# lcd_booster-old.net
KiCad netlist of a schematic drawn in EAGLE
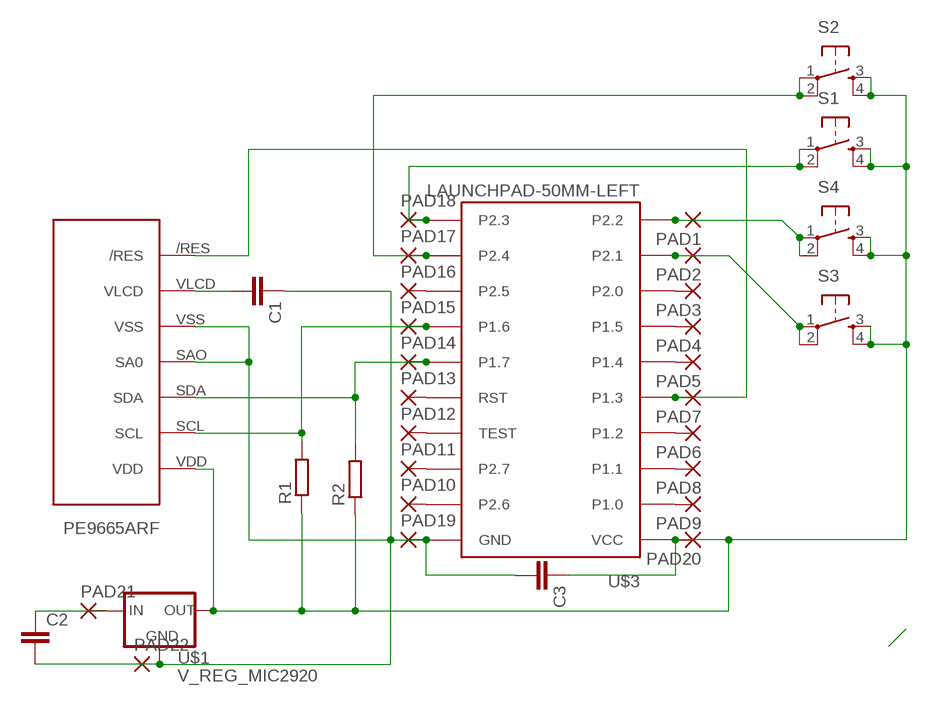
[diagram p0: schematic, sheet 1]

(export (version "E")
  (design (tool "Eeschema 10.0.6"))
  (components
    (comp (ref "C1")
      (value "C-EUC1206")
      (footprint "eagle-import:C1206")
      (libsource (lib "eagle-import") (part "C-EUC1206"))
    )
    (comp (ref "C2")
      (value "C-EUC1206")
      (footprint "eagle-import:C1206")
      (libsource (lib "eagle-import") (part "C-EUC1206"))
    )
    (comp (ref "C3")
      (value "C-EUC1206")
      (footprint "eagle-import:C1206")
      (libsource (lib "eagle-import") (part "C-EUC1206"))
    )
    (comp (ref "PAD1")
      (value "1,6/0,9")
      (footprint "eagle-import:1,6_0,9")
      (libsource (lib "eagle-import") (part "1,6/0,9"))
    )
    (comp (ref "PAD2")
      (value "1,6/0,9")
      (footprint "eagle-import:1,6_0,9")
      (libsource (lib "eagle-import") (part "1,6/0,9"))
    )
    (comp (ref "PAD3")
      (value "1,6/0,9")
      (footprint "eagle-import:1,6_0,9")
      (libsource (lib "eagle-import") (part "1,6/0,9"))
    )
    (comp (ref "PAD4")
      (value "1,6/0,9")
      (footprint "eagle-import:1,6_0,9")
      (libsource (lib "eagle-import") (part "1,6/0,9"))
    )
    (comp (ref "PAD5")
      (value "1,6/0,9")
      (footprint "eagle-import:1,6_0,9")
      (libsource (lib "eagle-import") (part "1,6/0,9"))
    )
    (comp (ref "PAD6")
      (value "1,6/0,9")
      (footprint "eagle-import:1,6_0,9")
      (libsource (lib "eagle-import") (part "1,6/0,9"))
    )
    (comp (ref "PAD7")
      (value "1,6/0,9")
      (footprint "eagle-import:1,6_0,9")
      (libsource (lib "eagle-import") (part "1,6/0,9"))
    )
    (comp (ref "PAD8")
      (value "1,6/0,9")
      (footprint "eagle-import:1,6_0,9")
      (libsource (lib "eagle-import") (part "1,6/0,9"))
    )
    (comp (ref "PAD9")
      (value "1,6/0,9")
      (footprint "eagle-import:1,6_0,9")
      (libsource (lib "eagle-import") (part "1,6/0,9"))
    )
    (comp (ref "PAD10")
      (value "1,6/0,9")
      (footprint "eagle-import:1,6_0,9")
      (libsource (lib "eagle-import") (part "1,6/0,9"))
    )
    (comp (ref "PAD11")
      (value "1,6/0,9")
      (footprint "eagle-import:1,6_0,9")
      (libsource (lib "eagle-import") (part "1,6/0,9"))
    )
    (comp (ref "PAD12")
      (value "1,6/0,9")
      (footprint "eagle-import:1,6_0,9")
      (libsource (lib "eagle-import") (part "1,6/0,9"))
    )
    (comp (ref "PAD13")
      (value "1,6/0,9")
      (footprint "eagle-import:1,6_0,9")
      (libsource (lib "eagle-import") (part "1,6/0,9"))
    )
    (comp (ref "PAD14")
      (value "1,6/0,9")
      (footprint "eagle-import:1,6_0,9")
      (libsource (lib "eagle-import") (part "1,6/0,9"))
    )
    (comp (ref "PAD15")
      (value "1,6/0,9")
      (footprint "eagle-import:1,6_0,9")
      (libsource (lib "eagle-import") (part "1,6/0,9"))
    )
    (comp (ref "PAD16")
      (value "1,6/0,9")
      (footprint "eagle-import:1,6_0,9")
      (libsource (lib "eagle-import") (part "1,6/0,9"))
    )
    (comp (ref "PAD17")
      (value "1,6/0,9")
      (footprint "eagle-import:1,6_0,9")
      (libsource (lib "eagle-import") (part "1,6/0,9"))
    )
    (comp (ref "PAD18")
      (value "1,6/0,9")
      (footprint "eagle-import:1,6_0,9")
      (libsource (lib "eagle-import") (part "1,6/0,9"))
    )
    (comp (ref "PAD19")
      (value "1,6/0,9")
      (footprint "eagle-import:1,6_0,9")
      (libsource (lib "eagle-import") (part "1,6/0,9"))
    )
    (comp (ref "PAD20")
      (value "1,6/0,9")
      (footprint "eagle-import:1,6_0,9")
      (libsource (lib "eagle-import") (part "1,6/0,9"))
    )
    (comp (ref "PAD21")
      (value "1,6/0,9")
      (footprint "eagle-import:1,6_0,9")
      (libsource (lib "eagle-import") (part "1,6/0,9"))
    )
    (comp (ref "PAD22")
      (value "1,6/0,9")
      (footprint "eagle-import:1,6_0,9")
      (libsource (lib "eagle-import") (part "1,6/0,9"))
    )
    (comp (ref "R1")
      (value "R-EU_M1206")
      (footprint "eagle-import:M1206")
      (libsource (lib "eagle-import") (part "R-EU_M1206"))
    )
    (comp (ref "R2")
      (value "R-EU_M1206")
      (footprint "eagle-import:M1206")
      (libsource (lib "eagle-import") (part "R-EU_M1206"))
    )
    (comp (ref "S1")
      (value "TAC_SWITCHPTH")
      (footprint "eagle-import:TACTILE-PTH")
      (libsource (lib "eagle-import") (part "TAC_SWITCHPTH"))
    )
    (comp (ref "S2")
      (value "TAC_SWITCHPTH")
      (footprint "eagle-import:TACTILE-PTH")
      (libsource (lib "eagle-import") (part "TAC_SWITCHPTH"))
    )
    (comp (ref "S3")
      (value "TAC_SWITCHPTH")
      (footprint "eagle-import:TACTILE-PTH")
      (libsource (lib "eagle-import") (part "TAC_SWITCHPTH"))
    )
    (comp (ref "S4")
      (value "TAC_SWITCHPTH")
      (footprint "eagle-import:TACTILE-PTH")
      (libsource (lib "eagle-import") (part "TAC_SWITCHPTH"))
    )
    (comp (ref "U$1")
      (value "V_REG_MIC2920")
      (footprint "eagle-import:SOT223")
      (libsource (lib "eagle-import") (part "V_REG_MIC2920"))
    )
    (comp (ref "U$2")
      (value "PE9665ARF")
      (footprint "eagle-import:PE9665ARF")
      (libsource (lib "eagle-import") (part "PE9665ARF"))
    )
    (comp (ref "U$3")
      (value "LAUNCHPAD-50MM-LEFT")
      (footprint "eagle-import:LAUNCHPAD-50MM-LEFT")
      (libsource (lib "eagle-import") (part "LAUNCHPAD-50MM-LEFT"))
    )
  )
  (nets
    (net (code "1") (name "Net-(C1-Pad2)") (class "Default")
      (node (ref "C1") (pin "2") (pinfunction "2_2") (pintype "passive"))
      (node (ref "U$2") (pin "VLCD") (pinfunction "VLCD_VLCD") (pintype "bidirectional"))
    )
    (net (code "2") (name "Net-(PAD1-P)") (class "Default")
      (node (ref "PAD1") (pin "1") (pinfunction "P_1") (pintype "passive"))
      (node (ref "S4") (pin "1") (pinfunction "1_1") (pintype "passive"))
      (node (ref "S4") (pin "2") (pinfunction "2_2") (pintype "passive"))
      (node (ref "U$3") (pin "P2.2") (pinfunction "P2.2_P2.2") (pintype "bidirectional"))
    )
    (net (code "3") (name "Net-(PAD2-P)") (class "Default")
      (node (ref "PAD2") (pin "1") (pinfunction "P_1") (pintype "passive"))
      (node (ref "S3") (pin "1") (pinfunction "1_1") (pintype "passive"))
      (node (ref "S3") (pin "2") (pinfunction "2_2") (pintype "passive"))
      (node (ref "U$3") (pin "P2.1") (pinfunction "P2.1_P2.1") (pintype "bidirectional"))
    )
    (net (code "4") (name "Net-(PAD3-P)") (class "Default")
      (node (ref "PAD3") (pin "1") (pinfunction "P_1") (pintype "passive"))
      (node (ref "U$3") (pin "P2.0") (pinfunction "P2.0_P2.0") (pintype "bidirectional"))
    )
    (net (code "5") (name "Net-(PAD4-P)") (class "Default")
      (node (ref "PAD4") (pin "1") (pinfunction "P_1") (pintype "passive"))
      (node (ref "U$3") (pin "P1.5") (pinfunction "P1.5_P1.5") (pintype "bidirectional"))
    )
    (net (code "6") (name "Net-(PAD5-P)") (class "Default")
      (node (ref "PAD5") (pin "1") (pinfunction "P_1") (pintype "passive"))
      (node (ref "U$3") (pin "P1.4") (pinfunction "P1.4_P1.4") (pintype "bidirectional"))
    )
    (net (code "7") (name "Net-(PAD6-P)") (class "Default")
      (node (ref "PAD6") (pin "1") (pinfunction "P_1") (pintype "passive"))
      (node (ref "U$3") (pin "P1.2") (pinfunction "P1.2_P1.2") (pintype "bidirectional"))
    )
    (net (code "8") (name "Net-(PAD7-P)") (class "Default")
      (node (ref "PAD7") (pin "1") (pinfunction "P_1") (pintype "passive"))
      (node (ref "U$2") (pin "/RES") (pinfunction "/RES_/RES") (pintype "bidirectional"))
      (node (ref "U$3") (pin "P1.3") (pinfunction "P1.3_P1.3") (pintype "bidirectional"))
    )
    (net (code "9") (name "Net-(PAD8-P)") (class "Default")
      (node (ref "PAD8") (pin "1") (pinfunction "P_1") (pintype "passive"))
      (node (ref "U$3") (pin "P1.1") (pinfunction "P1.1_P1.1") (pintype "bidirectional"))
    )
    (net (code "10") (name "Net-(PAD9-P)") (class "Default")
      (node (ref "PAD9") (pin "1") (pinfunction "P_1") (pintype "passive"))
      (node (ref "U$3") (pin "P1.0") (pinfunction "P1.0_P1.0") (pintype "bidirectional"))
    )
    (net (code "11") (name "Net-(PAD10-P)") (class "Default")
      (node (ref "PAD10") (pin "1") (pinfunction "P_1") (pintype "passive"))
      (node (ref "U$3") (pin "P2.6") (pinfunction "P2.6_P2.6") (pintype "bidirectional"))
    )
    (net (code "12") (name "Net-(PAD11-P)") (class "Default")
      (node (ref "PAD11") (pin "1") (pinfunction "P_1") (pintype "passive"))
      (node (ref "U$3") (pin "P2.7") (pinfunction "P2.7_P2.7") (pintype "bidirectional"))
    )
    (net (code "13") (name "Net-(PAD12-P)") (class "Default")
      (node (ref "PAD12") (pin "1") (pinfunction "P_1") (pintype "passive"))
      (node (ref "U$3") (pin "TEST") (pinfunction "TEST_TEST") (pintype "bidirectional"))
    )
    (net (code "14") (name "Net-(PAD13-P)") (class "Default")
      (node (ref "PAD13") (pin "1") (pinfunction "P_1") (pintype "passive"))
      (node (ref "U$3") (pin "RST") (pinfunction "RST_RST") (pintype "bidirectional"))
    )
    (net (code "15") (name "Net-(PAD14-P)") (class "Default")
      (node (ref "PAD14") (pin "1") (pinfunction "P_1") (pintype "passive"))
      (node (ref "R2") (pin "2") (pinfunction "2_2") (pintype "passive"))
      (node (ref "U$2") (pin "SDA") (pinfunction "SDA_SDA") (pintype "bidirectional"))
      (node (ref "U$3") (pin "P1.7") (pinfunction "P1.7_P1.7") (pintype "bidirectional"))
    )
    (net (code "16") (name "Net-(PAD15-P)") (class "Default")
      (node (ref "PAD15") (pin "1") (pinfunction "P_1") (pintype "passive"))
      (node (ref "R1") (pin "2") (pinfunction "2_2") (pintype "passive"))
      (node (ref "U$2") (pin "SCL") (pinfunction "SCL_SCL") (pintype "bidirectional"))
      (node (ref "U$3") (pin "P1.6") (pinfunction "P1.6_P1.6") (pintype "bidirectional"))
    )
    (net (code "17") (name "Net-(PAD16-P)") (class "Default")
      (node (ref "PAD16") (pin "1") (pinfunction "P_1") (pintype "passive"))
      (node (ref "U$3") (pin "P2.5") (pinfunction "P2.5_P2.5") (pintype "bidirectional"))
    )
    (net (code "18") (name "Net-(PAD17-P)") (class "Default")
      (node (ref "PAD17") (pin "1") (pinfunction "P_1") (pintype "passive"))
      (node (ref "S2") (pin "1") (pinfunction "1_1") (pintype "passive"))
      (node (ref "S2") (pin "2") (pinfunction "2_2") (pintype "passive"))
      (node (ref "U$3") (pin "P2.4") (pinfunction "P2.4_P2.4") (pintype "bidirectional"))
    )
    (net (code "19") (name "Net-(PAD18-P)") (class "Default")
      (node (ref "PAD18") (pin "1") (pinfunction "P_1") (pintype "passive"))
      (node (ref "S1") (pin "1") (pinfunction "1_1") (pintype "passive"))
      (node (ref "S1") (pin "2") (pinfunction "2_2") (pintype "passive"))
      (node (ref "U$3") (pin "P2.3") (pinfunction "P2.3_P2.3") (pintype "bidirectional"))
    )
    (net (code "20") (name "Net-(PAD19-P)") (class "Default")
      (node (ref "C1") (pin "1") (pinfunction "1_1") (pintype "passive"))
      (node (ref "C2") (pin "2") (pinfunction "2_2") (pintype "passive"))
      (node (ref "C3") (pin "2") (pinfunction "2_2") (pintype "passive"))
      (node (ref "PAD19") (pin "1") (pinfunction "P_1") (pintype "passive"))
      (node (ref "PAD22") (pin "1") (pinfunction "P_1") (pintype "passive"))
      (node (ref "U$1") (pin "2") (pinfunction "GND_2") (pintype "input"))
      (node (ref "U$2") (pin "SAO") (pinfunction "SA0_SAO") (pintype "bidirectional"))
      (node (ref "U$2") (pin "VSS") (pinfunction "VSS_VSS") (pintype "power_in"))
      (node (ref "U$3") (pin "GND") (pinfunction "GND_GND") (pintype "power_in"))
    )
    (net (code "21") (name "Net-(PAD20-P)") (class "Default")
      (node (ref "C3") (pin "1") (pinfunction "1_1") (pintype "passive"))
      (node (ref "PAD20") (pin "1") (pinfunction "P_1") (pintype "passive"))
      (node (ref "R1") (pin "1") (pinfunction "1_1") (pintype "passive"))
      (node (ref "R2") (pin "1") (pinfunction "1_1") (pintype "passive"))
      (node (ref "S1") (pin "3") (pinfunction "3_3") (pintype "passive"))
      (node (ref "S1") (pin "4") (pinfunction "4_4") (pintype "passive"))
      (node (ref "S2") (pin "3") (pinfunction "3_3") (pintype "passive"))
      (node (ref "S2") (pin "4") (pinfunction "4_4") (pintype "passive"))
      (node (ref "S3") (pin "3") (pinfunction "3_3") (pintype "passive"))
      (node (ref "S3") (pin "4") (pinfunction "4_4") (pintype "passive"))
      (node (ref "S4") (pin "3") (pinfunction "3_3") (pintype "passive"))
      (node (ref "S4") (pin "4") (pinfunction "4_4") (pintype "passive"))
      (node (ref "U$1") (pin "3") (pinfunction "OUT_3") (pintype "output"))
      (node (ref "U$2") (pin "VDD") (pinfunction "VDD_VDD") (pintype "power_in"))
      (node (ref "U$3") (pin "VCC") (pinfunction "VCC_VCC") (pintype "power_in"))
    )
    (net (code "22") (name "Net-(PAD21-P)") (class "Default")
      (node (ref "C2") (pin "1") (pinfunction "1_1") (pintype "passive"))
      (node (ref "PAD21") (pin "1") (pinfunction "P_1") (pintype "passive"))
      (node (ref "U$1") (pin "1") (pinfunction "IN_1") (pintype "input"))
    )
  )
)
